# post_schematic_v4_charlieplex_v30.net
KiCad netlist of a schematic drawn in EAGLE
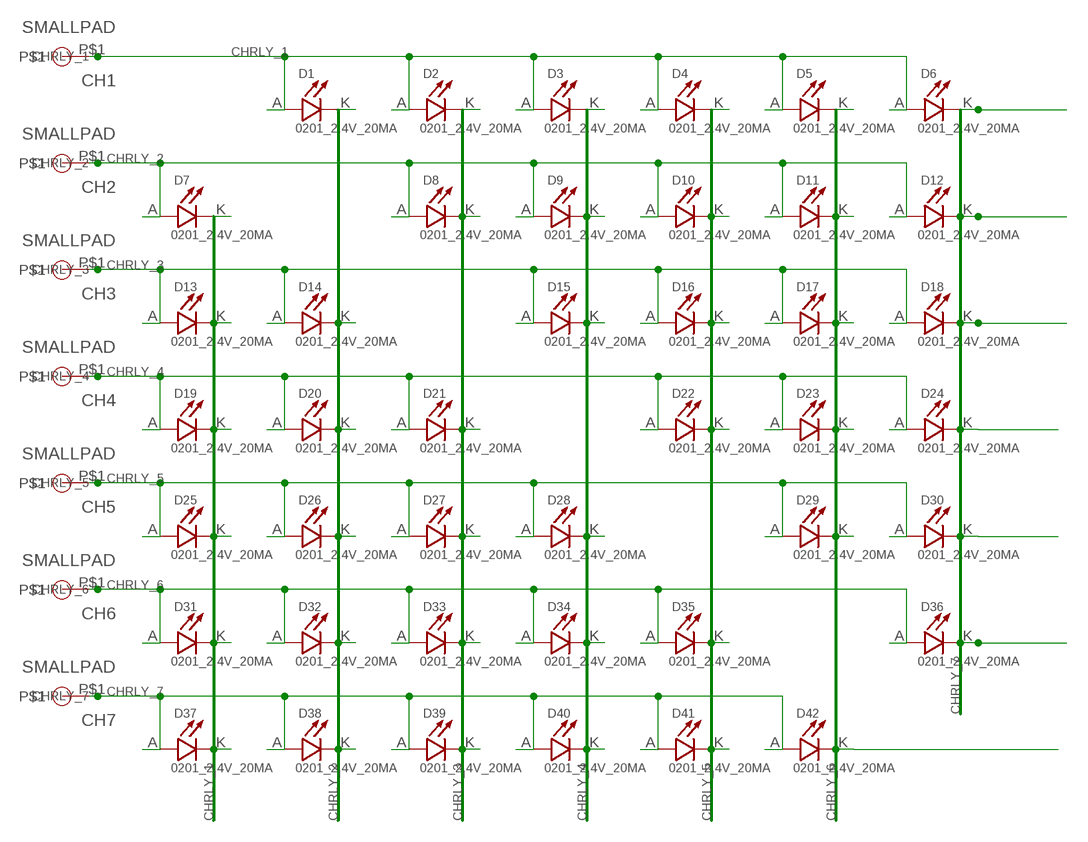
[diagram p0: schematic, sheet 1]
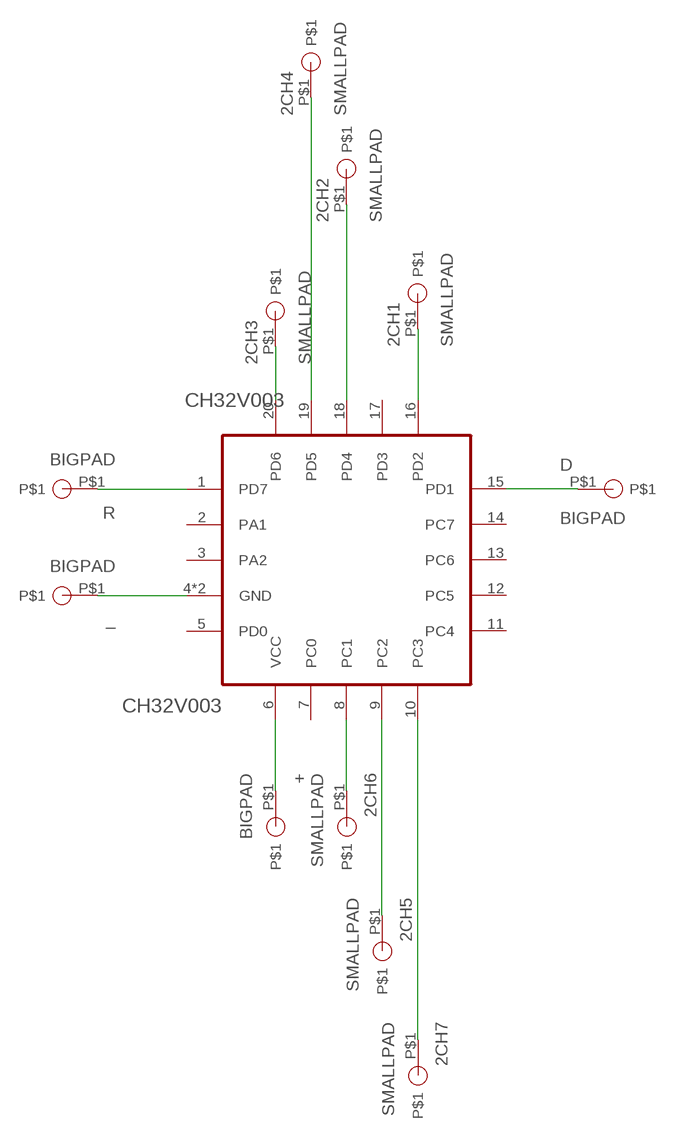
[diagram p1: schematic, sheet 2]

(export (version "E")
  (design (tool "Eeschema 10.0.6"))
  (components
    (comp (ref "CH1")
      (value "SMALLPAD")
      (footprint "eagle-import:SMALLPAD")
      (libsource (lib "eagle-import") (part "SMALLPAD"))
    )
    (comp (ref "CH2")
      (value "SMALLPAD")
      (footprint "eagle-import:SMALLPAD")
      (libsource (lib "eagle-import") (part "SMALLPAD"))
    )
    (comp (ref "CH3")
      (value "SMALLPAD")
      (footprint "eagle-import:SMALLPAD")
      (libsource (lib "eagle-import") (part "SMALLPAD"))
    )
    (comp (ref "CH4")
      (value "SMALLPAD")
      (footprint "eagle-import:SMALLPAD")
      (libsource (lib "eagle-import") (part "SMALLPAD"))
    )
    (comp (ref "CH5")
      (value "SMALLPAD")
      (footprint "eagle-import:SMALLPAD")
      (libsource (lib "eagle-import") (part "SMALLPAD"))
    )
    (comp (ref "CH6")
      (value "SMALLPAD")
      (footprint "eagle-import:SMALLPAD")
      (libsource (lib "eagle-import") (part "SMALLPAD"))
    )
    (comp (ref "CH7")
      (value "SMALLPAD")
      (footprint "eagle-import:SMALLPAD")
      (libsource (lib "eagle-import") (part "SMALLPAD"))
    )
    (comp (ref "D1")
      (value "0201_2.4V_20MA")
      (footprint "eagle-import:0201_2.4V_20MA")
      (fields (field (name "MF") "Kingbright") (field (name "MP") "APG0603CGC-TT"))
      (libsource (lib "eagle-import") (part "0201_2.4V_20MA"))
    )
    (comp (ref "D2")
      (value "0201_2.4V_20MA")
      (footprint "eagle-import:0201_2.4V_20MA")
      (fields (field (name "MF") "Kingbright") (field (name "MP") "APG0603CGC-TT"))
      (libsource (lib "eagle-import") (part "0201_2.4V_20MA"))
    )
    (comp (ref "D3")
      (value "0201_2.4V_20MA")
      (footprint "eagle-import:0201_2.4V_20MA")
      (fields (field (name "MF") "Kingbright") (field (name "MP") "APG0603CGC-TT"))
      (libsource (lib "eagle-import") (part "0201_2.4V_20MA"))
    )
    (comp (ref "D4")
      (value "0201_2.4V_20MA")
      (footprint "eagle-import:0201_2.4V_20MA")
      (fields (field (name "MF") "Kingbright") (field (name "MP") "APG0603CGC-TT"))
      (libsource (lib "eagle-import") (part "0201_2.4V_20MA"))
    )
    (comp (ref "D5")
      (value "0201_2.4V_20MA")
      (footprint "eagle-import:0201_2.4V_20MA")
      (fields (field (name "MF") "Kingbright") (field (name "MP") "APG0603CGC-TT"))
      (libsource (lib "eagle-import") (part "0201_2.4V_20MA"))
    )
    (comp (ref "D6")
      (value "0201_2.4V_20MA")
      (footprint "eagle-import:0201_2.4V_20MA")
      (fields (field (name "MF") "Kingbright") (field (name "MP") "APG0603CGC-TT"))
      (libsource (lib "eagle-import") (part "0201_2.4V_20MA"))
    )
    (comp (ref "D7")
      (value "0201_2.4V_20MA")
      (footprint "eagle-import:0201_2.4V_20MA")
      (fields (field (name "MF") "Kingbright") (field (name "MP") "APG0603CGC-TT"))
      (libsource (lib "eagle-import") (part "0201_2.4V_20MA"))
    )
    (comp (ref "D8")
      (value "0201_2.4V_20MA")
      (footprint "eagle-import:0201_2.4V_20MA")
      (fields (field (name "MF") "Kingbright") (field (name "MP") "APG0603CGC-TT"))
      (libsource (lib "eagle-import") (part "0201_2.4V_20MA"))
    )
    (comp (ref "D9")
      (value "0201_2.4V_20MA")
      (footprint "eagle-import:0201_2.4V_20MA")
      (fields (field (name "MF") "Kingbright") (field (name "MP") "APG0603CGC-TT"))
      (libsource (lib "eagle-import") (part "0201_2.4V_20MA"))
    )
    (comp (ref "D10")
      (value "0201_2.4V_20MA")
      (footprint "eagle-import:0201_2.4V_20MA")
      (fields (field (name "MF") "Kingbright") (field (name "MP") "APG0603CGC-TT"))
      (libsource (lib "eagle-import") (part "0201_2.4V_20MA"))
    )
    (comp (ref "D11")
      (value "0201_2.4V_20MA")
      (footprint "eagle-import:0201_2.4V_20MA")
      (fields (field (name "MF") "Kingbright") (field (name "MP") "APG0603CGC-TT"))
      (libsource (lib "eagle-import") (part "0201_2.4V_20MA"))
    )
    (comp (ref "D12")
      (value "0201_2.4V_20MA")
      (footprint "eagle-import:0201_2.4V_20MA")
      (fields (field (name "MF") "Kingbright") (field (name "MP") "APG0603CGC-TT"))
      (libsource (lib "eagle-import") (part "0201_2.4V_20MA"))
    )
    (comp (ref "D13")
      (value "0201_2.4V_20MA")
      (footprint "eagle-import:0201_2.4V_20MA")
      (fields (field (name "MF") "Kingbright") (field (name "MP") "APG0603CGC-TT"))
      (libsource (lib "eagle-import") (part "0201_2.4V_20MA"))
    )
    (comp (ref "D14")
      (value "0201_2.4V_20MA")
      (footprint "eagle-import:0201_2.4V_20MA")
      (fields (field (name "MF") "Kingbright") (field (name "MP") "APG0603CGC-TT"))
      (libsource (lib "eagle-import") (part "0201_2.4V_20MA"))
    )
    (comp (ref "D15")
      (value "0201_2.4V_20MA")
      (footprint "eagle-import:0201_2.4V_20MA")
      (fields (field (name "MF") "Kingbright") (field (name "MP") "APG0603CGC-TT"))
      (libsource (lib "eagle-import") (part "0201_2.4V_20MA"))
    )
    (comp (ref "D16")
      (value "0201_2.4V_20MA")
      (footprint "eagle-import:0201_2.4V_20MA")
      (fields (field (name "MF") "Kingbright") (field (name "MP") "APG0603CGC-TT"))
      (libsource (lib "eagle-import") (part "0201_2.4V_20MA"))
    )
    (comp (ref "D17")
      (value "0201_2.4V_20MA")
      (footprint "eagle-import:0201_2.4V_20MA")
      (fields (field (name "MF") "Kingbright") (field (name "MP") "APG0603CGC-TT"))
      (libsource (lib "eagle-import") (part "0201_2.4V_20MA"))
    )
    (comp (ref "D18")
      (value "0201_2.4V_20MA")
      (footprint "eagle-import:0201_2.4V_20MA")
      (fields (field (name "MF") "Kingbright") (field (name "MP") "APG0603CGC-TT"))
      (libsource (lib "eagle-import") (part "0201_2.4V_20MA"))
    )
    (comp (ref "D19")
      (value "0201_2.4V_20MA")
      (footprint "eagle-import:0201_2.4V_20MA")
      (fields (field (name "MF") "Kingbright") (field (name "MP") "APG0603CGC-TT"))
      (libsource (lib "eagle-import") (part "0201_2.4V_20MA"))
    )
    (comp (ref "D20")
      (value "0201_2.4V_20MA")
      (footprint "eagle-import:0201_2.4V_20MA")
      (fields (field (name "MF") "Kingbright") (field (name "MP") "APG0603CGC-TT"))
      (libsource (lib "eagle-import") (part "0201_2.4V_20MA"))
    )
    (comp (ref "D21")
      (value "0201_2.4V_20MA")
      (footprint "eagle-import:0201_2.4V_20MA")
      (fields (field (name "MF") "Kingbright") (field (name "MP") "APG0603CGC-TT"))
      (libsource (lib "eagle-import") (part "0201_2.4V_20MA"))
    )
    (comp (ref "D22")
      (value "0201_2.4V_20MA")
      (footprint "eagle-import:0201_2.4V_20MA")
      (fields (field (name "MF") "Kingbright") (field (name "MP") "APG0603CGC-TT"))
      (libsource (lib "eagle-import") (part "0201_2.4V_20MA"))
    )
    (comp (ref "D23")
      (value "0201_2.4V_20MA")
      (footprint "eagle-import:0201_2.4V_20MA")
      (fields (field (name "MF") "Kingbright") (field (name "MP") "APG0603CGC-TT"))
      (libsource (lib "eagle-import") (part "0201_2.4V_20MA"))
    )
    (comp (ref "D24")
      (value "0201_2.4V_20MA")
      (footprint "eagle-import:0201_2.4V_20MA")
      (fields (field (name "MF") "Kingbright") (field (name "MP") "APG0603CGC-TT"))
      (libsource (lib "eagle-import") (part "0201_2.4V_20MA"))
    )
    (comp (ref "D25")
      (value "0201_2.4V_20MA")
      (footprint "eagle-import:0201_2.4V_20MA")
      (fields (field (name "MF") "Kingbright") (field (name "MP") "APG0603CGC-TT"))
      (libsource (lib "eagle-import") (part "0201_2.4V_20MA"))
    )
    (comp (ref "D26")
      (value "0201_2.4V_20MA")
      (footprint "eagle-import:0201_2.4V_20MA")
      (fields (field (name "MF") "Kingbright") (field (name "MP") "APG0603CGC-TT"))
      (libsource (lib "eagle-import") (part "0201_2.4V_20MA"))
    )
    (comp (ref "D27")
      (value "0201_2.4V_20MA")
      (footprint "eagle-import:0201_2.4V_20MA")
      (fields (field (name "MF") "Kingbright") (field (name "MP") "APG0603CGC-TT"))
      (libsource (lib "eagle-import") (part "0201_2.4V_20MA"))
    )
    (comp (ref "D28")
      (value "0201_2.4V_20MA")
      (footprint "eagle-import:0201_2.4V_20MA")
      (fields (field (name "MF") "Kingbright") (field (name "MP") "APG0603CGC-TT"))
      (libsource (lib "eagle-import") (part "0201_2.4V_20MA"))
    )
    (comp (ref "D29")
      (value "0201_2.4V_20MA")
      (footprint "eagle-import:0201_2.4V_20MA")
      (fields (field (name "MF") "Kingbright") (field (name "MP") "APG0603CGC-TT"))
      (libsource (lib "eagle-import") (part "0201_2.4V_20MA"))
    )
    (comp (ref "D30")
      (value "0201_2.4V_20MA")
      (footprint "eagle-import:0201_2.4V_20MA")
      (fields (field (name "MF") "Kingbright") (field (name "MP") "APG0603CGC-TT"))
      (libsource (lib "eagle-import") (part "0201_2.4V_20MA"))
    )
    (comp (ref "D31")
      (value "0201_2.4V_20MA")
      (footprint "eagle-import:0201_2.4V_20MA")
      (fields (field (name "MF") "Kingbright") (field (name "MP") "APG0603CGC-TT"))
      (libsource (lib "eagle-import") (part "0201_2.4V_20MA"))
    )
    (comp (ref "D32")
      (value "0201_2.4V_20MA")
      (footprint "eagle-import:0201_2.4V_20MA")
      (fields (field (name "MF") "Kingbright") (field (name "MP") "APG0603CGC-TT"))
      (libsource (lib "eagle-import") (part "0201_2.4V_20MA"))
    )
    (comp (ref "D33")
      (value "0201_2.4V_20MA")
      (footprint "eagle-import:0201_2.4V_20MA")
      (fields (field (name "MF") "Kingbright") (field (name "MP") "APG0603CGC-TT"))
      (libsource (lib "eagle-import") (part "0201_2.4V_20MA"))
    )
    (comp (ref "D34")
      (value "0201_2.4V_20MA")
      (footprint "eagle-import:0201_2.4V_20MA")
      (fields (field (name "MF") "Kingbright") (field (name "MP") "APG0603CGC-TT"))
      (libsource (lib "eagle-import") (part "0201_2.4V_20MA"))
    )
    (comp (ref "D35")
      (value "0201_2.4V_20MA")
      (footprint "eagle-import:0201_2.4V_20MA")
      (fields (field (name "MF") "Kingbright") (field (name "MP") "APG0603CGC-TT"))
      (libsource (lib "eagle-import") (part "0201_2.4V_20MA"))
    )
    (comp (ref "D36")
      (value "0201_2.4V_20MA")
      (footprint "eagle-import:0201_2.4V_20MA")
      (fields (field (name "MF") "Kingbright") (field (name "MP") "APG0603CGC-TT"))
      (libsource (lib "eagle-import") (part "0201_2.4V_20MA"))
    )
    (comp (ref "D37")
      (value "0201_2.4V_20MA")
      (footprint "eagle-import:0201_2.4V_20MA")
      (fields (field (name "MF") "Kingbright") (field (name "MP") "APG0603CGC-TT"))
      (libsource (lib "eagle-import") (part "0201_2.4V_20MA"))
    )
    (comp (ref "D38")
      (value "0201_2.4V_20MA")
      (footprint "eagle-import:0201_2.4V_20MA")
      (fields (field (name "MF") "Kingbright") (field (name "MP") "APG0603CGC-TT"))
      (libsource (lib "eagle-import") (part "0201_2.4V_20MA"))
    )
    (comp (ref "D39")
      (value "0201_2.4V_20MA")
      (footprint "eagle-import:0201_2.4V_20MA")
      (fields (field (name "MF") "Kingbright") (field (name "MP") "APG0603CGC-TT"))
      (libsource (lib "eagle-import") (part "0201_2.4V_20MA"))
    )
    (comp (ref "D40")
      (value "0201_2.4V_20MA")
      (footprint "eagle-import:0201_2.4V_20MA")
      (fields (field (name "MF") "Kingbright") (field (name "MP") "APG0603CGC-TT"))
      (libsource (lib "eagle-import") (part "0201_2.4V_20MA"))
    )
    (comp (ref "D41")
      (value "0201_2.4V_20MA")
      (footprint "eagle-import:0201_2.4V_20MA")
      (fields (field (name "MF") "Kingbright") (field (name "MP") "APG0603CGC-TT"))
      (libsource (lib "eagle-import") (part "0201_2.4V_20MA"))
    )
    (comp (ref "D42")
      (value "0201_2.4V_20MA")
      (footprint "eagle-import:0201_2.4V_20MA")
      (fields (field (name "MF") "Kingbright") (field (name "MP") "APG0603CGC-TT"))
      (libsource (lib "eagle-import") (part "0201_2.4V_20MA"))
    )
    (comp (ref "+")
      (value "BIGPAD")
      (footprint "eagle-import:BIGPAD")
      (libsource (lib "eagle-import") (part "BIGPAD"))
    )
    (comp (ref "2CH1")
      (value "SMALLPAD")
      (footprint "eagle-import:SMALLPAD")
      (libsource (lib "eagle-import") (part "SMALLPAD"))
    )
    (comp (ref "2CH2")
      (value "SMALLPAD")
      (footprint "eagle-import:SMALLPAD")
      (libsource (lib "eagle-import") (part "SMALLPAD"))
    )
    (comp (ref "2CH3")
      (value "SMALLPAD")
      (footprint "eagle-import:SMALLPAD")
      (libsource (lib "eagle-import") (part "SMALLPAD"))
    )
    (comp (ref "2CH4")
      (value "SMALLPAD")
      (footprint "eagle-import:SMALLPAD")
      (libsource (lib "eagle-import") (part "SMALLPAD"))
    )
    (comp (ref "2CH5")
      (value "SMALLPAD")
      (footprint "eagle-import:SMALLPAD")
      (libsource (lib "eagle-import") (part "SMALLPAD"))
    )
    (comp (ref "2CH6")
      (value "SMALLPAD")
      (footprint "eagle-import:SMALLPAD")
      (libsource (lib "eagle-import") (part "SMALLPAD"))
    )
    (comp (ref "2CH7")
      (value "SMALLPAD")
      (footprint "eagle-import:SMALLPAD")
      (libsource (lib "eagle-import") (part "SMALLPAD"))
    )
    (comp (ref "CH32V003")
      (value "CH32V003")
      (footprint "eagle-import:QFN40P300X300X90-21N")
      (fields (field (name "MF") "Microchip Technology") (field (name "MP") "ATTINY816-MF"))
      (libsource (lib "eagle-import") (part "CH32V003"))
    )
    (comp (ref "D")
      (value "BIGPAD")
      (footprint "eagle-import:BIGPAD")
      (libsource (lib "eagle-import") (part "BIGPAD"))
    )
    (comp (ref "R")
      (value "BIGPAD")
      (footprint "eagle-import:BIGPAD")
      (libsource (lib "eagle-import") (part "BIGPAD"))
    )
    (comp (ref "_")
      (value "BIGPAD")
      (footprint "eagle-import:BIGPAD")
      (libsource (lib "eagle-import") (part "BIGPAD"))
    )
  )
  (nets
    (net (code "1") (name "CHRLY_1") (class "Default")
      (node (ref "CH1") (pin "P$1") (pinfunction "P$1_P$1") (pintype "bidirectional"))
      (node (ref "D1") (pin "A") (pinfunction "A_A") (pintype "passive"))
      (node (ref "D13") (pin "K") (pinfunction "K_K") (pintype "passive"))
      (node (ref "D19") (pin "K") (pinfunction "K_K") (pintype "passive"))
      (node (ref "D2") (pin "A") (pinfunction "A_A") (pintype "passive"))
      (node (ref "D25") (pin "K") (pinfunction "K_K") (pintype "passive"))
      (node (ref "D3") (pin "A") (pinfunction "A_A") (pintype "passive"))
      (node (ref "D31") (pin "K") (pinfunction "K_K") (pintype "passive"))
      (node (ref "D37") (pin "K") (pinfunction "K_K") (pintype "passive"))
      (node (ref "D4") (pin "A") (pinfunction "A_A") (pintype "passive"))
      (node (ref "D5") (pin "A") (pinfunction "A_A") (pintype "passive"))
      (node (ref "D6") (pin "A") (pinfunction "A_A") (pintype "passive"))
      (node (ref "D7") (pin "K") (pinfunction "K_K") (pintype "passive"))
    )
    (net (code "2") (name "CHRLY_2") (class "Default")
      (node (ref "CH2") (pin "P$1") (pinfunction "P$1_P$1") (pintype "bidirectional"))
      (node (ref "D1") (pin "K") (pinfunction "K_K") (pintype "passive"))
      (node (ref "D10") (pin "A") (pinfunction "A_A") (pintype "passive"))
      (node (ref "D11") (pin "A") (pinfunction "A_A") (pintype "passive"))
      (node (ref "D12") (pin "A") (pinfunction "A_A") (pintype "passive"))
      (node (ref "D14") (pin "K") (pinfunction "K_K") (pintype "passive"))
      (node (ref "D20") (pin "K") (pinfunction "K_K") (pintype "passive"))
      (node (ref "D26") (pin "K") (pinfunction "K_K") (pintype "passive"))
      (node (ref "D32") (pin "K") (pinfunction "K_K") (pintype "passive"))
      (node (ref "D38") (pin "K") (pinfunction "K_K") (pintype "passive"))
      (node (ref "D7") (pin "A") (pinfunction "A_A") (pintype "passive"))
      (node (ref "D8") (pin "A") (pinfunction "A_A") (pintype "passive"))
      (node (ref "D9") (pin "A") (pinfunction "A_A") (pintype "passive"))
    )
    (net (code "3") (name "CHRLY_3") (class "Default")
      (node (ref "CH3") (pin "P$1") (pinfunction "P$1_P$1") (pintype "bidirectional"))
      (node (ref "D13") (pin "A") (pinfunction "A_A") (pintype "passive"))
      (node (ref "D14") (pin "A") (pinfunction "A_A") (pintype "passive"))
      (node (ref "D15") (pin "A") (pinfunction "A_A") (pintype "passive"))
      (node (ref "D16") (pin "A") (pinfunction "A_A") (pintype "passive"))
      (node (ref "D17") (pin "A") (pinfunction "A_A") (pintype "passive"))
      (node (ref "D18") (pin "A") (pinfunction "A_A") (pintype "passive"))
      (node (ref "D2") (pin "K") (pinfunction "K_K") (pintype "passive"))
      (node (ref "D21") (pin "K") (pinfunction "K_K") (pintype "passive"))
      (node (ref "D27") (pin "K") (pinfunction "K_K") (pintype "passive"))
      (node (ref "D33") (pin "K") (pinfunction "K_K") (pintype "passive"))
      (node (ref "D39") (pin "K") (pinfunction "K_K") (pintype "passive"))
      (node (ref "D8") (pin "K") (pinfunction "K_K") (pintype "passive"))
    )
    (net (code "4") (name "CHRLY_4") (class "Default")
      (node (ref "CH4") (pin "P$1") (pinfunction "P$1_P$1") (pintype "bidirectional"))
      (node (ref "D15") (pin "K") (pinfunction "K_K") (pintype "passive"))
      (node (ref "D19") (pin "A") (pinfunction "A_A") (pintype "passive"))
      (node (ref "D20") (pin "A") (pinfunction "A_A") (pintype "passive"))
      (node (ref "D21") (pin "A") (pinfunction "A_A") (pintype "passive"))
      (node (ref "D22") (pin "A") (pinfunction "A_A") (pintype "passive"))
      (node (ref "D23") (pin "A") (pinfunction "A_A") (pintype "passive"))
      (node (ref "D24") (pin "A") (pinfunction "A_A") (pintype "passive"))
      (node (ref "D28") (pin "K") (pinfunction "K_K") (pintype "passive"))
      (node (ref "D3") (pin "K") (pinfunction "K_K") (pintype "passive"))
      (node (ref "D34") (pin "K") (pinfunction "K_K") (pintype "passive"))
      (node (ref "D40") (pin "K") (pinfunction "K_K") (pintype "passive"))
      (node (ref "D9") (pin "K") (pinfunction "K_K") (pintype "passive"))
    )
    (net (code "5") (name "CHRLY_5") (class "Default")
      (node (ref "CH5") (pin "P$1") (pinfunction "P$1_P$1") (pintype "bidirectional"))
      (node (ref "D10") (pin "K") (pinfunction "K_K") (pintype "passive"))
      (node (ref "D16") (pin "K") (pinfunction "K_K") (pintype "passive"))
      (node (ref "D22") (pin "K") (pinfunction "K_K") (pintype "passive"))
      (node (ref "D25") (pin "A") (pinfunction "A_A") (pintype "passive"))
      (node (ref "D26") (pin "A") (pinfunction "A_A") (pintype "passive"))
      (node (ref "D27") (pin "A") (pinfunction "A_A") (pintype "passive"))
      (node (ref "D28") (pin "A") (pinfunction "A_A") (pintype "passive"))
      (node (ref "D29") (pin "A") (pinfunction "A_A") (pintype "passive"))
      (node (ref "D30") (pin "A") (pinfunction "A_A") (pintype "passive"))
      (node (ref "D35") (pin "K") (pinfunction "K_K") (pintype "passive"))
      (node (ref "D4") (pin "K") (pinfunction "K_K") (pintype "passive"))
      (node (ref "D41") (pin "K") (pinfunction "K_K") (pintype "passive"))
    )
    (net (code "6") (name "CHRLY_6") (class "Default")
      (node (ref "CH6") (pin "P$1") (pinfunction "P$1_P$1") (pintype "bidirectional"))
      (node (ref "D11") (pin "K") (pinfunction "K_K") (pintype "passive"))
      (node (ref "D17") (pin "K") (pinfunction "K_K") (pintype "passive"))
      (node (ref "D23") (pin "K") (pinfunction "K_K") (pintype "passive"))
      (node (ref "D29") (pin "K") (pinfunction "K_K") (pintype "passive"))
      (node (ref "D31") (pin "A") (pinfunction "A_A") (pintype "passive"))
      (node (ref "D32") (pin "A") (pinfunction "A_A") (pintype "passive"))
      (node (ref "D33") (pin "A") (pinfunction "A_A") (pintype "passive"))
      (node (ref "D34") (pin "A") (pinfunction "A_A") (pintype "passive"))
      (node (ref "D35") (pin "A") (pinfunction "A_A") (pintype "passive"))
      (node (ref "D36") (pin "A") (pinfunction "A_A") (pintype "passive"))
      (node (ref "D42") (pin "K") (pinfunction "K_K") (pintype "passive"))
      (node (ref "D5") (pin "K") (pinfunction "K_K") (pintype "passive"))
    )
    (net (code "7") (name "CHRLY_7") (class "Default")
      (node (ref "CH7") (pin "P$1") (pinfunction "P$1_P$1") (pintype "bidirectional"))
      (node (ref "D12") (pin "K") (pinfunction "K_K") (pintype "passive"))
      (node (ref "D18") (pin "K") (pinfunction "K_K") (pintype "passive"))
      (node (ref "D24") (pin "K") (pinfunction "K_K") (pintype "passive"))
      (node (ref "D30") (pin "K") (pinfunction "K_K") (pintype "passive"))
      (node (ref "D36") (pin "K") (pinfunction "K_K") (pintype "passive"))
      (node (ref "D37") (pin "A") (pinfunction "A_A") (pintype "passive"))
      (node (ref "D38") (pin "A") (pinfunction "A_A") (pintype "passive"))
      (node (ref "D39") (pin "A") (pinfunction "A_A") (pintype "passive"))
      (node (ref "D40") (pin "A") (pinfunction "A_A") (pintype "passive"))
      (node (ref "D41") (pin "A") (pinfunction "A_A") (pintype "passive"))
      (node (ref "D42") (pin "A") (pinfunction "A_A") (pintype "passive"))
      (node (ref "D6") (pin "K") (pinfunction "K_K") (pintype "passive"))
    )
    (net (code "8") (name "Net-(CH32V003-GND-Pad21)") (class "Default")
      (node (ref "CH32V003") (pin "21") (pinfunction "GND_21") (pintype "passive"))
      (node (ref "CH32V003") (pin "4") (pinfunction "GND_4") (pintype "passive"))
      (node (ref "_") (pin "P$1") (pinfunction "P$1_P$1") (pintype "bidirectional"))
    )
    (net (code "9") (name "Net-(CH32V003-PC1)") (class "Default")
      (node (ref "2CH6") (pin "P$1") (pinfunction "P$1_P$1") (pintype "bidirectional"))
      (node (ref "CH32V003") (pin "8") (pinfunction "PC1_8") (pintype "input"))
    )
    (net (code "10") (name "Net-(CH32V003-PC2)") (class "Default")
      (node (ref "2CH5") (pin "P$1") (pinfunction "P$1_P$1") (pintype "bidirectional"))
      (node (ref "CH32V003") (pin "9") (pinfunction "PC2_9") (pintype "input"))
    )
    (net (code "11") (name "Net-(CH32V003-PC3)") (class "Default")
      (node (ref "2CH7") (pin "P$1") (pinfunction "P$1_P$1") (pintype "bidirectional"))
      (node (ref "CH32V003") (pin "10") (pinfunction "PC3_10") (pintype "output"))
    )
    (net (code "12") (name "Net-(CH32V003-PD1)") (class "Default")
      (node (ref "CH32V003") (pin "15") (pinfunction "PD1_15") (pintype "output"))
      (node (ref "D") (pin "P$1") (pinfunction "P$1_P$1") (pintype "bidirectional"))
    )
    (net (code "13") (name "Net-(CH32V003-PD2)") (class "Default")
      (node (ref "2CH1") (pin "P$1") (pinfunction "P$1_P$1") (pintype "bidirectional"))
      (node (ref "CH32V003") (pin "16") (pinfunction "PD2_16") (pintype "output"))
    )
    (net (code "14") (name "Net-(CH32V003-PD4)") (class "Default")
      (node (ref "2CH2") (pin "P$1") (pinfunction "P$1_P$1") (pintype "bidirectional"))
      (node (ref "CH32V003") (pin "18") (pinfunction "PD4_18") (pintype "bidirectional"))
    )
    (net (code "15") (name "Net-(CH32V003-PD5)") (class "Default")
      (node (ref "2CH4") (pin "P$1") (pinfunction "P$1_P$1") (pintype "bidirectional"))
      (node (ref "CH32V003") (pin "19") (pinfunction "PD5_19") (pintype "input"))
    )
    (net (code "16") (name "Net-(CH32V003-PD6)") (class "Default")
      (node (ref "2CH3") (pin "P$1") (pinfunction "P$1_P$1") (pintype "bidirectional"))
      (node (ref "CH32V003") (pin "20") (pinfunction "PD6_20") (pintype "input"))
    )
    (net (code "17") (name "Net-(CH32V003-PD7)") (class "Default")
      (node (ref "CH32V003") (pin "1") (pinfunction "PD7_1") (pintype "input"))
      (node (ref "R") (pin "P$1") (pinfunction "P$1_P$1") (pintype "bidirectional"))
    )
    (net (code "18") (name "Net-(CH32V003-VCC)") (class "Default")
      (node (ref "+") (pin "P$1") (pinfunction "P$1_P$1") (pintype "bidirectional"))
      (node (ref "CH32V003") (pin "6") (pinfunction "VCC_6") (pintype "power_in"))
    )
    (net (code "19") (name "unconnected-(CH32V003-PA1-Pad2)") (class "Default")
      (node (ref "CH32V003") (pin "2") (pinfunction "PA1_2") (pintype "input"))
    )
    (net (code "20") (name "unconnected-(CH32V003-PA2-Pad3)") (class "Default")
      (node (ref "CH32V003") (pin "3") (pinfunction "PA2_3") (pintype "input"))
    )
    (net (code "21") (name "unconnected-(CH32V003-PC0-Pad7)") (class "Default")
      (node (ref "CH32V003") (pin "7") (pinfunction "PC0_7") (pintype "input"))
    )
    (net (code "22") (name "unconnected-(CH32V003-PC4-Pad11)") (class "Default")
      (node (ref "CH32V003") (pin "11") (pinfunction "PC4_11") (pintype "output"))
    )
    (net (code "23") (name "unconnected-(CH32V003-PC5-Pad12)") (class "Default")
      (node (ref "CH32V003") (pin "12") (pinfunction "PC5_12") (pintype "output"))
    )
    (net (code "24") (name "unconnected-(CH32V003-PC6-Pad13)") (class "Default")
      (node (ref "CH32V003") (pin "13") (pinfunction "PC6_13") (pintype "output"))
    )
    (net (code "25") (name "unconnected-(CH32V003-PC7-Pad14)") (class "Default")
      (node (ref "CH32V003") (pin "14") (pinfunction "PC7_14") (pintype "output"))
    )
    (net (code "26") (name "unconnected-(CH32V003-PD0-Pad5)") (class "Default")
      (node (ref "CH32V003") (pin "5") (pinfunction "PD0_5") (pintype "input"))
    )
    (net (code "27") (name "unconnected-(CH32V003-PD3-Pad17)") (class "Default")
      (node (ref "CH32V003") (pin "17") (pinfunction "PD3_17") (pintype "output"))
    )
  )
)
